# esp_garden_v2.net
KiCad netlist of a schematic drawn in EAGLE
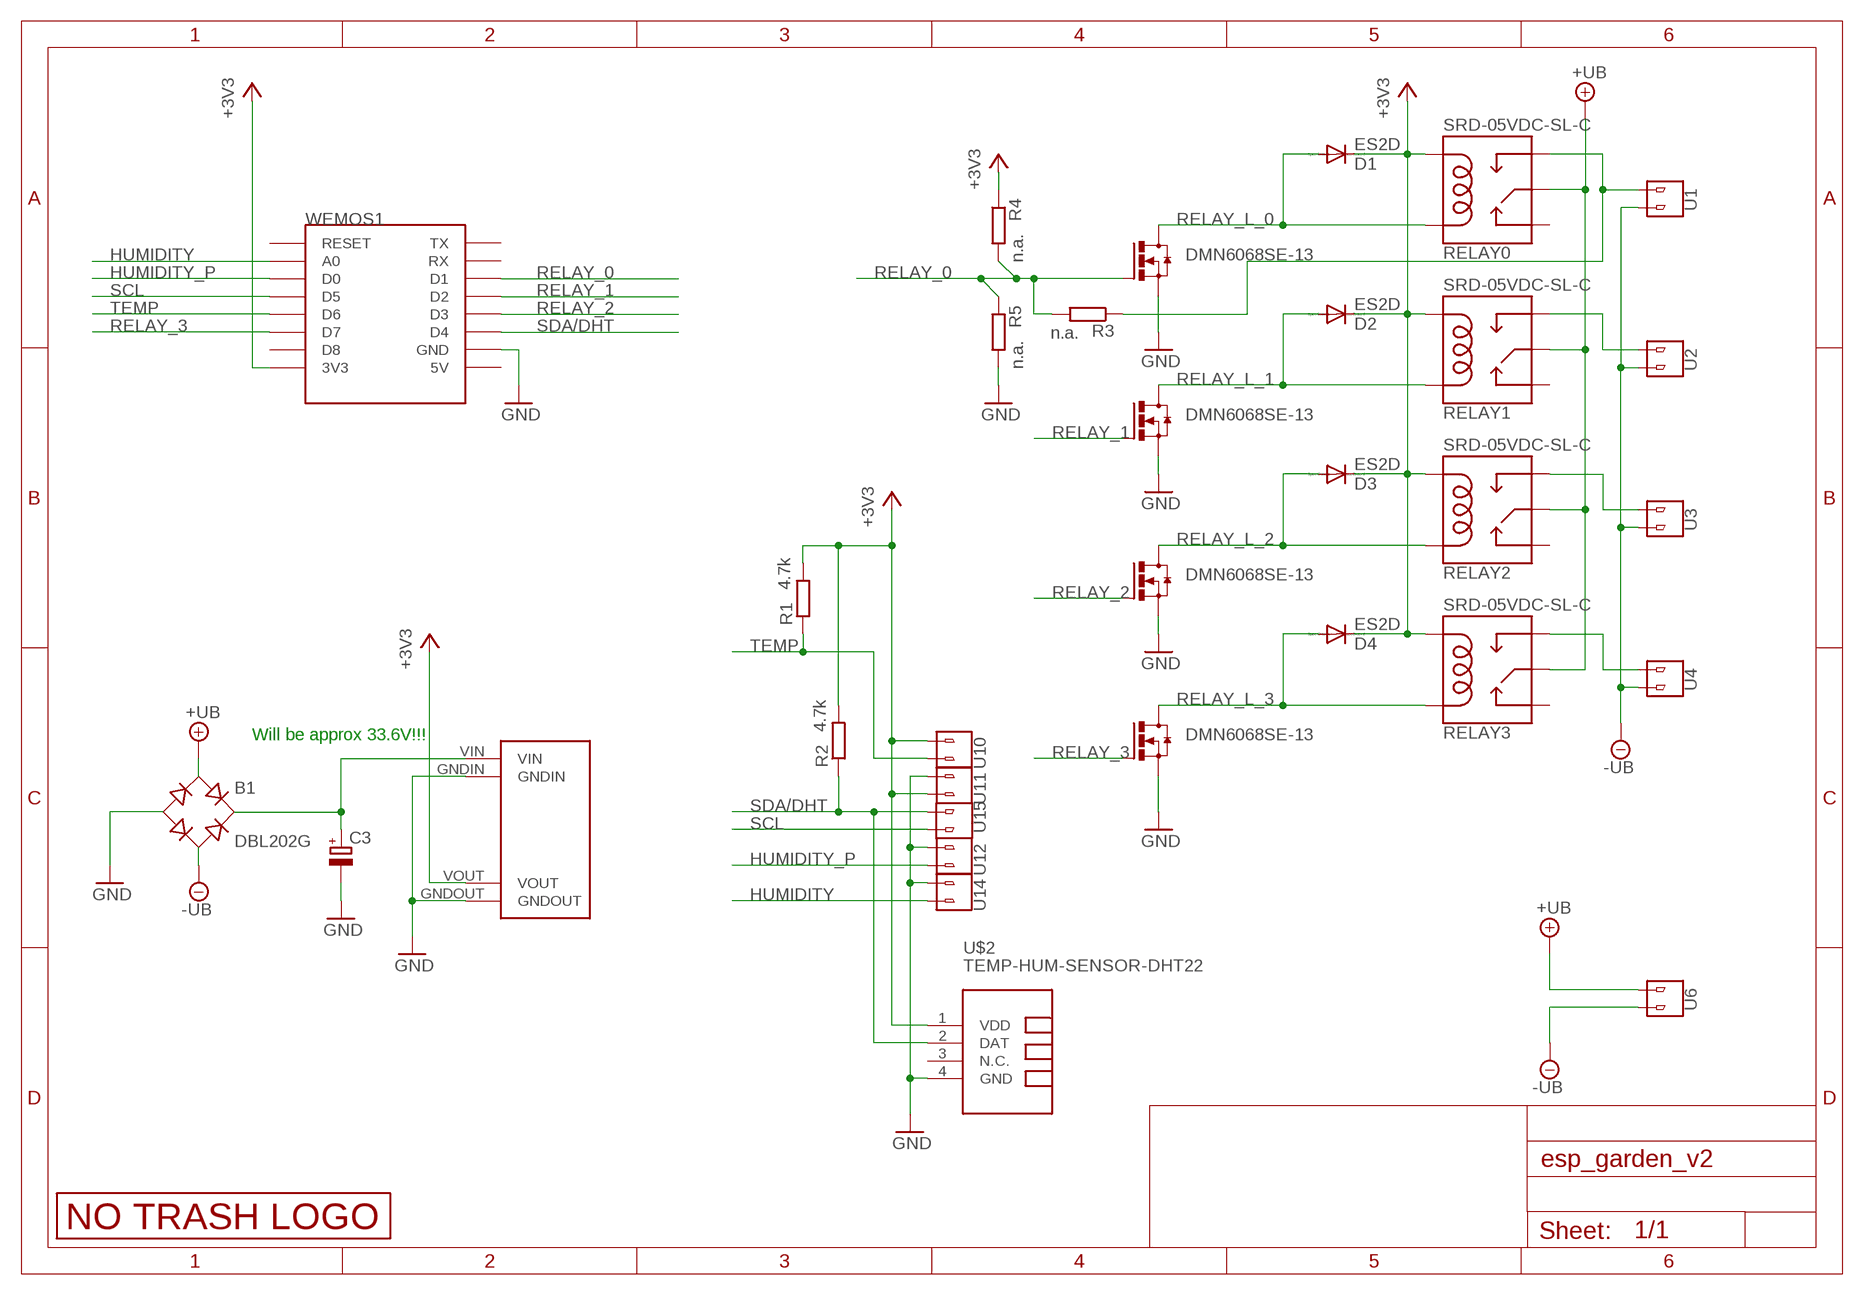
[diagram p0: schematic, sheet 1]

(export (version "E")
  (design (tool "Eeschema 10.0.6"))
  (components
    (comp (ref "B1")
      (value "DBL202G")
      (footprint "eagle-import:DB")
      (libsource (lib "eagle-import") (part "DB?GL202"))
    )
    (comp (ref "C3")
      (value "CPOL-EU150CLZ-0810")
      (footprint "eagle-import:150CLZ-0810")
      (libsource (lib "eagle-import") (part "CPOL-EU150CLZ-0810"))
    )
    (comp (ref "D1")
      (value "ES2D")
      (footprint "eagle-import:SMB")
      (libsource (lib "eagle-import") (part "DIODE-SMB"))
    )
    (comp (ref "D2")
      (value "ES2D")
      (footprint "eagle-import:SMB")
      (libsource (lib "eagle-import") (part "DIODE-SMB"))
    )
    (comp (ref "D3")
      (value "ES2D")
      (footprint "eagle-import:SMB")
      (libsource (lib "eagle-import") (part "DIODE-SMB"))
    )
    (comp (ref "D4")
      (value "ES2D")
      (footprint "eagle-import:SMB")
      (libsource (lib "eagle-import") (part "DIODE-SMB"))
    )
    (comp (ref "R1")
      (value "4.7k")
      (footprint "eagle-import:M0805")
      (libsource (lib "eagle-import") (part "R-EU_M0805"))
    )
    (comp (ref "R2")
      (value "4.7k")
      (footprint "eagle-import:M0805")
      (libsource (lib "eagle-import") (part "R-EU_M0805"))
    )
    (comp (ref "R3")
      (value "n.a.")
      (footprint "eagle-import:M0805")
      (libsource (lib "eagle-import") (part "R-EU_M0805"))
    )
    (comp (ref "R4")
      (value "n.a.")
      (footprint "eagle-import:M0805")
      (libsource (lib "eagle-import") (part "R-EU_M0805"))
    )
    (comp (ref "R5")
      (value "n.a.")
      (footprint "eagle-import:M0805")
      (libsource (lib "eagle-import") (part "R-EU_M0805"))
    )
    (comp (ref "RELAY0")
      (value "SRD-05VDC-SL-C")
      (footprint "eagle-import:SRD-05VDC-SL-C")
      (libsource (lib "eagle-import") (part "RELAYPTH"))
    )
    (comp (ref "RELAY1")
      (value "SRD-05VDC-SL-C")
      (footprint "eagle-import:SRD-05VDC-SL-C")
      (libsource (lib "eagle-import") (part "RELAYPTH"))
    )
    (comp (ref "RELAY2")
      (value "SRD-05VDC-SL-C")
      (footprint "eagle-import:SRD-05VDC-SL-C")
      (libsource (lib "eagle-import") (part "RELAYPTH"))
    )
    (comp (ref "RELAY3")
      (value "SRD-05VDC-SL-C")
      (footprint "eagle-import:SRD-05VDC-SL-C")
      (libsource (lib "eagle-import") (part "RELAYPTH"))
    )
    (comp (ref "T1")
      (value "DMN6068SE-13")
      (footprint "eagle-import:SOT223")
      (libsource (lib "eagle-import") (part "NMOSFET_SMD_223"))
    )
    (comp (ref "T2")
      (value "DMN6068SE-13")
      (footprint "eagle-import:SOT223")
      (libsource (lib "eagle-import") (part "NMOSFET_SMD_223"))
    )
    (comp (ref "T3")
      (value "DMN6068SE-13")
      (footprint "eagle-import:SOT223")
      (libsource (lib "eagle-import") (part "NMOSFET_SMD_223"))
    )
    (comp (ref "T4")
      (value "DMN6068SE-13")
      (footprint "eagle-import:SOT223")
      (libsource (lib "eagle-import") (part "NMOSFET_SMD_223"))
    )
    (comp (ref "U$1")
      (value "LOGO_NO_TRASHNO_TRASH")
      (footprint "eagle-import:LOGO_ROHS_NO_TRASH")
      (libsource (lib "eagle-import") (part "LOGO_NO_TRASHNO_TRASH"))
    )
    (comp (ref "U$2")
      (value "TEMP-HUM-SENSOR-DHT22")
      (footprint "eagle-import:TEMP-HUM-SENSOR-DHT22")
      (libsource (lib "eagle-import") (part "TEMP-HUM-SENSOR-DHT22"))
    )
    (comp (ref "U$3")
      (value "MP1584EN")
      (footprint "eagle-import:MP1584EN")
      (libsource (lib "eagle-import") (part "MP1584EN"))
    )
    (comp (ref "U1")
      (value "V1")
      (footprint "eagle-import:2_SCREW_PIN")
      (libsource (lib "eagle-import") (part "2_PIN_CONNECTOR"))
    )
    (comp (ref "U2")
      (value "V1")
      (footprint "eagle-import:2_SCREW_PIN")
      (libsource (lib "eagle-import") (part "2_PIN_CONNECTOR"))
    )
    (comp (ref "U3")
      (value "V1")
      (footprint "eagle-import:2_SCREW_PIN")
      (libsource (lib "eagle-import") (part "2_PIN_CONNECTOR"))
    )
    (comp (ref "U4")
      (value "V1")
      (footprint "eagle-import:2_SCREW_PIN")
      (libsource (lib "eagle-import") (part "2_PIN_CONNECTOR"))
    )
    (comp (ref "U6")
      (value "V1")
      (footprint "eagle-import:2_SCREW_PIN")
      (libsource (lib "eagle-import") (part "2_PIN_CONNECTOR"))
    )
    (comp (ref "U10")
      (value "V1")
      (footprint "eagle-import:2_SCREW_PIN")
      (libsource (lib "eagle-import") (part "2_PIN_CONNECTOR"))
    )
    (comp (ref "U11")
      (value "V1")
      (footprint "eagle-import:2_SCREW_PIN")
      (libsource (lib "eagle-import") (part "2_PIN_CONNECTOR"))
    )
    (comp (ref "U12")
      (value "V1")
      (footprint "eagle-import:2_SCREW_PIN")
      (libsource (lib "eagle-import") (part "2_PIN_CONNECTOR"))
    )
    (comp (ref "U14")
      (value "V1")
      (footprint "eagle-import:2_SCREW_PIN")
      (libsource (lib "eagle-import") (part "2_PIN_CONNECTOR"))
    )
    (comp (ref "U15")
      (value "V1")
      (footprint "eagle-import:2_SCREW_PIN")
      (libsource (lib "eagle-import") (part "2_PIN_CONNECTOR"))
    )
    (comp (ref "WEMOS1")
      (value "WEMOS-D1-MINI")
      (footprint "eagle-import:WEMOS-D1-MINI")
      (libsource (lib "eagle-import") (part "WEMOS-D1-MINI"))
    )
  )
  (nets
    (net (code "1") (name "+3V3") (class "Default")
      (node (ref "D1") (pin "C") (pinfunction "C_C") (pintype "passive"))
      (node (ref "D2") (pin "C") (pinfunction "C_C") (pintype "passive"))
      (node (ref "D3") (pin "C") (pinfunction "C_C") (pintype "passive"))
      (node (ref "D4") (pin "C") (pinfunction "C_C") (pintype "passive"))
      (node (ref "R1") (pin "2") (pinfunction "2_2") (pintype "passive"))
      (node (ref "R2") (pin "2") (pinfunction "2_2") (pintype "passive"))
      (node (ref "R4") (pin "1") (pinfunction "1_1") (pintype "passive"))
      (node (ref "RELAY0") (pin "COIL0") (pinfunction "COIL0_COIL0") (pintype "bidirectional"))
      (node (ref "RELAY1") (pin "COIL0") (pinfunction "COIL0_COIL0") (pintype "bidirectional"))
      (node (ref "RELAY2") (pin "COIL0") (pinfunction "COIL0_COIL0") (pintype "bidirectional"))
      (node (ref "RELAY3") (pin "COIL0") (pinfunction "COIL0_COIL0") (pintype "bidirectional"))
      (node (ref "U$2") (pin "1") (pinfunction "VDD_1") (pintype "power_in"))
      (node (ref "U$3") (pin "VOUT") (pinfunction "VOUT_VOUT") (pintype "power_in"))
      (node (ref "U10") (pin "P$2") (pinfunction "2_P$2") (pintype "passive"))
      (node (ref "U11") (pin "P$1") (pinfunction "1_P$1") (pintype "passive"))
      (node (ref "WEMOS1") (pin "3V3") (pinfunction "3V3_3V3") (pintype "bidirectional"))
    )
    (net (code "2") (name "+UB") (class "Default")
      (node (ref "B1") (pin "AC1") (pinfunction "AC1_AC1") (pintype "passive"))
      (node (ref "RELAY0") (pin "SWCOMMON") (pinfunction "SWCOMMON_SWCOMMON") (pintype "bidirectional"))
      (node (ref "RELAY1") (pin "SWCOMMON") (pinfunction "SWCOMMON_SWCOMMON") (pintype "bidirectional"))
      (node (ref "RELAY2") (pin "SWCOMMON") (pinfunction "SWCOMMON_SWCOMMON") (pintype "bidirectional"))
      (node (ref "RELAY3") (pin "SWCOMMON") (pinfunction "SWCOMMON_SWCOMMON") (pintype "bidirectional"))
      (node (ref "U6") (pin "P$1") (pinfunction "1_P$1") (pintype "passive"))
    )
    (net (code "3") (name "-UB") (class "Default")
      (node (ref "B1") (pin "AC2") (pinfunction "AC2_AC2") (pintype "passive"))
      (node (ref "U1") (pin "P$2") (pinfunction "2_P$2") (pintype "passive"))
      (node (ref "U2") (pin "P$2") (pinfunction "2_P$2") (pintype "passive"))
      (node (ref "U3") (pin "P$2") (pinfunction "2_P$2") (pintype "passive"))
      (node (ref "U4") (pin "P$2") (pinfunction "2_P$2") (pintype "passive"))
      (node (ref "U6") (pin "P$2") (pinfunction "2_P$2") (pintype "passive"))
    )
    (net (code "4") (name "/HUMIDITY") (class "Default")
      (node (ref "U14") (pin "P$1") (pinfunction "1_P$1") (pintype "passive"))
      (node (ref "WEMOS1") (pin "A0") (pinfunction "A0_A0") (pintype "bidirectional"))
    )
    (net (code "5") (name "/HUMIDITY_P") (class "Default")
      (node (ref "U12") (pin "P$1") (pinfunction "1_P$1") (pintype "passive"))
      (node (ref "WEMOS1") (pin "D0") (pinfunction "D0_D0") (pintype "bidirectional"))
    )
    (net (code "6") (name "/RELAY_0") (class "Default")
      (node (ref "R3") (pin "2") (pinfunction "2_2") (pintype "passive"))
      (node (ref "R4") (pin "2") (pinfunction "2_2") (pintype "passive"))
      (node (ref "R5") (pin "1") (pinfunction "1_1") (pintype "passive"))
      (node (ref "T1") (pin "1") (pinfunction "G_1") (pintype "passive"))
      (node (ref "WEMOS1") (pin "D1") (pinfunction "D1_D1") (pintype "bidirectional"))
    )
    (net (code "7") (name "/RELAY_1") (class "Default")
      (node (ref "T2") (pin "1") (pinfunction "G_1") (pintype "passive"))
      (node (ref "WEMOS1") (pin "D2") (pinfunction "D2_D2") (pintype "bidirectional"))
    )
    (net (code "8") (name "/RELAY_2") (class "Default")
      (node (ref "T3") (pin "1") (pinfunction "G_1") (pintype "passive"))
      (node (ref "WEMOS1") (pin "D3") (pinfunction "D3_D3") (pintype "bidirectional"))
    )
    (net (code "9") (name "/RELAY_3") (class "Default")
      (node (ref "T4") (pin "1") (pinfunction "G_1") (pintype "passive"))
      (node (ref "WEMOS1") (pin "D7") (pinfunction "D7_D7") (pintype "bidirectional"))
    )
    (net (code "10") (name "/RELAY_L_0") (class "Default")
      (node (ref "D1") (pin "A") (pinfunction "A_A") (pintype "passive"))
      (node (ref "RELAY0") (pin "COIL1") (pinfunction "COIL1_COIL1") (pintype "bidirectional"))
      (node (ref "T1") (pin "2") (pinfunction "D_2") (pintype "passive"))
      (node (ref "T1") (pin "4") (pinfunction "D_4") (pintype "passive"))
    )
    (net (code "11") (name "/RELAY_L_1") (class "Default")
      (node (ref "D2") (pin "A") (pinfunction "A_A") (pintype "passive"))
      (node (ref "RELAY1") (pin "COIL1") (pinfunction "COIL1_COIL1") (pintype "bidirectional"))
      (node (ref "T2") (pin "2") (pinfunction "D_2") (pintype "passive"))
      (node (ref "T2") (pin "4") (pinfunction "D_4") (pintype "passive"))
    )
    (net (code "12") (name "/RELAY_L_2") (class "Default")
      (node (ref "D3") (pin "A") (pinfunction "A_A") (pintype "passive"))
      (node (ref "RELAY2") (pin "COIL1") (pinfunction "COIL1_COIL1") (pintype "bidirectional"))
      (node (ref "T3") (pin "2") (pinfunction "D_2") (pintype "passive"))
      (node (ref "T3") (pin "4") (pinfunction "D_4") (pintype "passive"))
    )
    (net (code "13") (name "/RELAY_L_3") (class "Default")
      (node (ref "D4") (pin "A") (pinfunction "A_A") (pintype "passive"))
      (node (ref "RELAY3") (pin "COIL1") (pinfunction "COIL1_COIL1") (pintype "bidirectional"))
      (node (ref "T4") (pin "2") (pinfunction "D_2") (pintype "passive"))
      (node (ref "T4") (pin "4") (pinfunction "D_4") (pintype "passive"))
    )
    (net (code "14") (name "/SCL") (class "Default")
      (node (ref "U15") (pin "P$2") (pinfunction "2_P$2") (pintype "passive"))
      (node (ref "WEMOS1") (pin "D5") (pinfunction "D5_D5") (pintype "bidirectional"))
    )
    (net (code "15") (name "/SDA{slash}DHT") (class "Default")
      (node (ref "R2") (pin "1") (pinfunction "1_1") (pintype "passive"))
      (node (ref "U$2") (pin "2") (pinfunction "DAT_2") (pintype "bidirectional"))
      (node (ref "U15") (pin "P$1") (pinfunction "1_P$1") (pintype "passive"))
      (node (ref "WEMOS1") (pin "D4") (pinfunction "D4_D4") (pintype "bidirectional"))
    )
    (net (code "16") (name "/TEMP") (class "Default")
      (node (ref "R1") (pin "1") (pinfunction "1_1") (pintype "passive"))
      (node (ref "U10") (pin "P$1") (pinfunction "1_P$1") (pintype "passive"))
      (node (ref "WEMOS1") (pin "D6") (pinfunction "D6_D6") (pintype "bidirectional"))
    )
    (net (code "17") (name "GND") (class "Default")
      (node (ref "B1") (pin "-") (pinfunction "-_-") (pintype "passive"))
      (node (ref "C3") (pin "-") (pinfunction "-_-") (pintype "passive"))
      (node (ref "R5") (pin "2") (pinfunction "2_2") (pintype "passive"))
      (node (ref "T1") (pin "3") (pinfunction "S_3") (pintype "passive"))
      (node (ref "T2") (pin "3") (pinfunction "S_3") (pintype "passive"))
      (node (ref "T3") (pin "3") (pinfunction "S_3") (pintype "passive"))
      (node (ref "T4") (pin "3") (pinfunction "S_3") (pintype "passive"))
      (node (ref "U$2") (pin "4") (pinfunction "GND_4") (pintype "power_in"))
      (node (ref "U$3") (pin "GNDIN") (pinfunction "GNDIN_GNDIN") (pintype "power_in"))
      (node (ref "U$3") (pin "GNDOUT") (pinfunction "GNDOUT_GNDOUT") (pintype "power_in"))
      (node (ref "U11") (pin "P$2") (pinfunction "2_P$2") (pintype "passive"))
      (node (ref "U12") (pin "P$2") (pinfunction "2_P$2") (pintype "passive"))
      (node (ref "U14") (pin "P$2") (pinfunction "2_P$2") (pintype "passive"))
      (node (ref "WEMOS1") (pin "GND") (pinfunction "GND_GND") (pintype "bidirectional"))
    )
    (net (code "18") (name "Net-(B1-Pad+)") (class "Default")
      (node (ref "B1") (pin "+") (pinfunction "+_+") (pintype "passive"))
      (node (ref "C3") (pin "+") (pinfunction "+_+") (pintype "passive"))
      (node (ref "U$3") (pin "VIN") (pinfunction "VIN_VIN") (pintype "power_in"))
    )
    (net (code "19") (name "Net-(U1-1)") (class "Default")
      (node (ref "R3") (pin "1") (pinfunction "1_1") (pintype "passive"))
      (node (ref "RELAY0") (pin "SWOPEN") (pinfunction "SWOPEN_SWOPEN") (pintype "bidirectional"))
      (node (ref "U1") (pin "P$1") (pinfunction "1_P$1") (pintype "passive"))
    )
    (net (code "20") (name "Net-(U2-1)") (class "Default")
      (node (ref "RELAY1") (pin "SWOPEN") (pinfunction "SWOPEN_SWOPEN") (pintype "bidirectional"))
      (node (ref "U2") (pin "P$1") (pinfunction "1_P$1") (pintype "passive"))
    )
    (net (code "21") (name "Net-(U3-1)") (class "Default")
      (node (ref "RELAY2") (pin "SWOPEN") (pinfunction "SWOPEN_SWOPEN") (pintype "bidirectional"))
      (node (ref "U3") (pin "P$1") (pinfunction "1_P$1") (pintype "passive"))
    )
    (net (code "22") (name "Net-(U4-1)") (class "Default")
      (node (ref "RELAY3") (pin "SWOPEN") (pinfunction "SWOPEN_SWOPEN") (pintype "bidirectional"))
      (node (ref "U4") (pin "P$1") (pinfunction "1_P$1") (pintype "passive"))
    )
    (net (code "23") (name "unconnected-(RELAY0-SWCLOSE-PadSWCLOSED)") (class "Default")
      (node (ref "RELAY0") (pin "SWCLOSED") (pinfunction "SWCLOSE_SWCLOSED") (pintype "bidirectional"))
    )
    (net (code "24") (name "unconnected-(RELAY1-SWCLOSE-PadSWCLOSED)") (class "Default")
      (node (ref "RELAY1") (pin "SWCLOSED") (pinfunction "SWCLOSE_SWCLOSED") (pintype "bidirectional"))
    )
    (net (code "25") (name "unconnected-(RELAY2-SWCLOSE-PadSWCLOSED)") (class "Default")
      (node (ref "RELAY2") (pin "SWCLOSED") (pinfunction "SWCLOSE_SWCLOSED") (pintype "bidirectional"))
    )
    (net (code "26") (name "unconnected-(RELAY3-SWCLOSE-PadSWCLOSED)") (class "Default")
      (node (ref "RELAY3") (pin "SWCLOSED") (pinfunction "SWCLOSE_SWCLOSED") (pintype "bidirectional"))
    )
    (net (code "27") (name "unconnected-(U$2-N.C.-Pad3)") (class "Default")
      (node (ref "U$2") (pin "3") (pinfunction "N.C._3") (pintype "passive"))
    )
    (net (code "28") (name "unconnected-(WEMOS1-Pad5V)") (class "Default")
      (node (ref "WEMOS1") (pin "5V") (pinfunction "5V_5V") (pintype "bidirectional"))
    )
    (net (code "29") (name "unconnected-(WEMOS1-PadD8)") (class "Default")
      (node (ref "WEMOS1") (pin "D8") (pinfunction "D8_D8") (pintype "bidirectional"))
    )
    (net (code "30") (name "unconnected-(WEMOS1-PadRESET)") (class "Default")
      (node (ref "WEMOS1") (pin "RESET") (pinfunction "RESET_RESET") (pintype "bidirectional"))
    )
    (net (code "31") (name "unconnected-(WEMOS1-PadRX)") (class "Default")
      (node (ref "WEMOS1") (pin "RX") (pinfunction "RX_RX") (pintype "bidirectional"))
    )
    (net (code "32") (name "unconnected-(WEMOS1-PadTX)") (class "Default")
      (node (ref "WEMOS1") (pin "TX") (pinfunction "TX_TX") (pintype "bidirectional"))
    )
  )
)
